# MicroControllerSTM32f103.net
KiCad netlist of a schematic drawn in Altium Designer
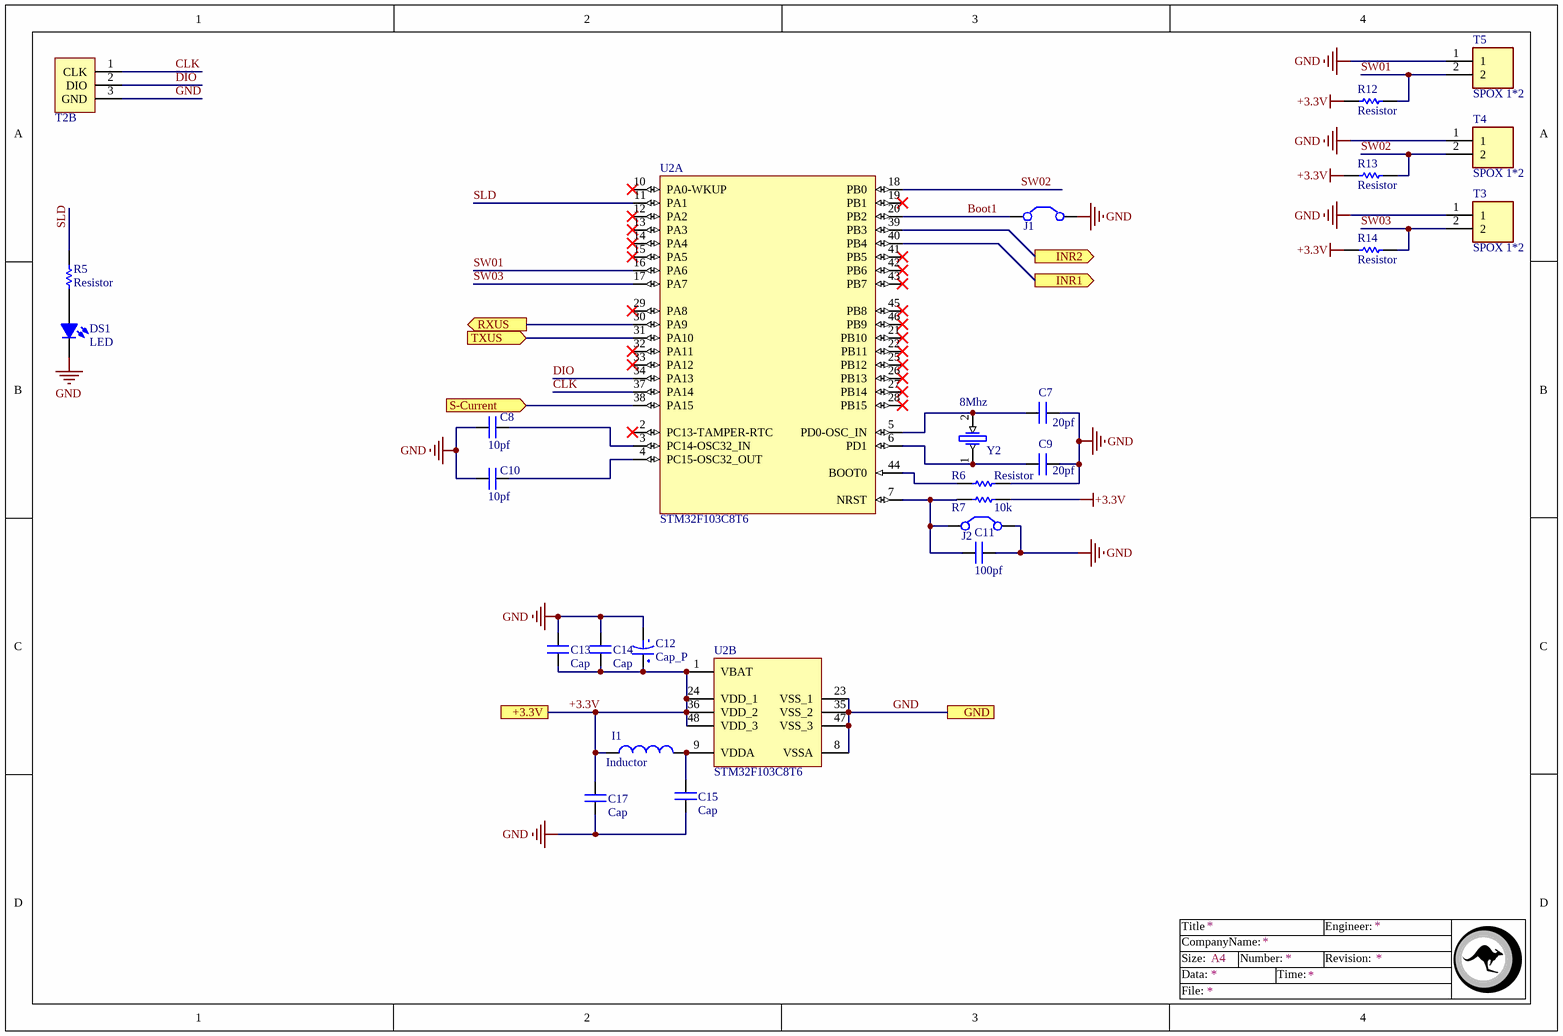
[diagram p0: MicroControllerSTM32f103.SchDoc]

(export (version "E")
  (design (tool "Eeschema 10.0.6"))
  (components
    (comp (ref "C7")
      (value "20pf")
      (footprint "Cap0805")
      (description "Surface mount Capacitor")
      (libsource (lib "PMLIB2020") (part "Cap"))
    )
    (comp (ref "C8")
      (value "10pf")
      (footprint "Cap0805")
      (description "Surface mount Capacitor")
      (libsource (lib "PMLIB2020") (part "Cap"))
    )
    (comp (ref "C9")
      (value "20pf")
      (footprint "Cap0805")
      (description "Surface mount Capacitor")
      (libsource (lib "PMLIB2020") (part "Cap"))
    )
    (comp (ref "C10")
      (value "10pf")
      (footprint "Cap0805")
      (description "Surface mount Capacitor")
      (libsource (lib "PMLIB2020") (part "Cap"))
    )
    (comp (ref "C11")
      (value "100pf")
      (footprint "Cap0805")
      (description "Surface mount Capacitor")
      (libsource (lib "PMLIB2020") (part "Cap"))
    )
    (comp (ref "C12")
      (value "Cap_P")
      (footprint "CAPMOL_C")
      (description "Polarity")
      (libsource (lib "PMLIB2020") (part "Cap_P"))
    )
    (comp (ref "C13")
      (value "Cap")
      (footprint "Cap0805")
      (description "Surface mount Capacitor")
      (libsource (lib "PMLIB2020") (part "Cap"))
    )
    (comp (ref "C14")
      (value "Cap")
      (footprint "Cap0805")
      (description "Surface mount Capacitor")
      (libsource (lib "PMLIB2020") (part "Cap"))
    )
    (comp (ref "C15")
      (value "Cap")
      (footprint "Cap0805")
      (description "Surface mount Capacitor")
      (libsource (lib "PMLIB2020") (part "Cap"))
    )
    (comp (ref "C17")
      (value "Cap")
      (footprint "Cap0805")
      (description "Surface mount Capacitor")
      (libsource (lib "PMLIB2020") (part "Cap"))
    )
    (comp (ref "DS1") (value "LED") (footprint "Led0805") (libsource (lib "PMLIB2020") (part "LED")))
    (comp (ref "I1")
      (value "Inductor")
      (footprint "1206")
      (description "Indicator")
      (libsource (lib "PMLIB2020") (part "Inductor"))
    )
    (comp (ref "J1")
      (value "Jumper")
      (footprint "Jumper SMD - Small")
      (libsource (lib "PMLIB2020") (part "Jumper"))
    )
    (comp (ref "J2")
      (value "Jumper")
      (footprint "Jumper SMD - Small")
      (libsource (lib "PMLIB2020") (part "Jumper"))
    )
    (comp (ref "R5") (value "Resistor") (footprint "R0805") (libsource (lib "PMLIB2020") (part "Resistor")))
    (comp (ref "R6") (value "Resistor") (footprint "R0805") (libsource (lib "PMLIB2020") (part "Resistor")))
    (comp (ref "R7")
      (value "10k")
      (footprint "R0805")
      (description "Resistor")
      (libsource (lib "PMLIB2020") (part "Resistor"))
    )
    (comp (ref "R12")
      (value "Resistor")
      (footprint "0603")
      (libsource (lib "PMLIB2020-V3") (part "Resistor"))
    )
    (comp (ref "R13")
      (value "Resistor")
      (footprint "0603")
      (libsource (lib "PMLIB2020-V3") (part "Resistor"))
    )
    (comp (ref "R14")
      (value "Resistor")
      (footprint "0603")
      (libsource (lib "PMLIB2020-V3") (part "Resistor"))
    )
    (comp (ref "T2")
      (value "Serial Program")
      (footprint "MHDR1X03-254P - E")
      (description "STM Serial Program pin")
      (libsource (lib "PMLIB2020") (part "Serial Program"))
    )
    (comp (ref "T3")
      (value "SPOX 1*2")
      (footprint "SPOX2")
      (libsource (lib "PMLIB2020-V3") (part "SPOX 1*2"))
    )
    (comp (ref "T4")
      (value "SPOX 1*2")
      (footprint "SPOX2")
      (libsource (lib "PMLIB2020-V3") (part "SPOX 1*2"))
    )
    (comp (ref "T5")
      (value "SPOX 1*2")
      (footprint "SPOX2")
      (libsource (lib "PMLIB2020-V3") (part "SPOX 1*2"))
    )
    (comp (ref "U2")
      (value "STM32F103C8T6")
      (footprint "LQFP48_L")
      (libsource (lib "STMicroelectronics STM32 F1") (part "STM32F103C8T6"))
    )
    (comp (ref "Y2")
      (value "8Mhz")
      (footprint "CrystallB")
      (description "Crystal")
      (libsource (lib "PMLIB2020") (part "Crystal"))
    )
  )
  (nets
    (net (code "1") (name "+3.3V") (class "Default")
      (node (ref "C12") (pin "2") (pinfunction "2_2") (pintype "passive"))
      (node (ref "C13") (pin "1") (pinfunction "1_1") (pintype "passive"))
      (node (ref "C14") (pin "1") (pinfunction "1_1") (pintype "passive"))
      (node (ref "C17") (pin "2") (pinfunction "2_2") (pintype "passive"))
      (node (ref "I1") (pin "1") (pinfunction "1_1") (pintype "passive"))
      (node (ref "R12") (pin "1") (pinfunction "1_1") (pintype "passive"))
      (node (ref "R13") (pin "1") (pinfunction "1_1") (pintype "passive"))
      (node (ref "R14") (pin "1") (pinfunction "1_1") (pintype "passive"))
      (node (ref "R7") (pin "1") (pinfunction "1_1") (pintype "passive"))
      (node (ref "U2") (pin "1") (pinfunction "VBAT_1") (pintype "power_in"))
      (node (ref "U2") (pin "24") (pinfunction "VDD_1_24") (pintype "power_in"))
      (node (ref "U2") (pin "36") (pinfunction "VDD_2_36") (pintype "power_in"))
      (node (ref "U2") (pin "48") (pinfunction "VDD_3_48") (pintype "power_in"))
    )
    (net (code "2") (name "/Boot1") (class "Default")
      (node (ref "J1") (pin "1") (pinfunction "C1_1") (pintype "passive"))
      (node (ref "U2") (pin "20") (pinfunction "PB2_20") (pintype "bidirectional"))
    )
    (net (code "3") (name "/CLK") (class "Default")
      (node (ref "T2") (pin "1") (pinfunction "CLK_1") (pintype "passive"))
      (node (ref "U2") (pin "37") (pinfunction "PA14_37") (pintype "bidirectional"))
    )
    (net (code "4") (name "/DIO") (class "Default")
      (node (ref "T2") (pin "2") (pinfunction "DIO_2") (pintype "passive"))
      (node (ref "U2") (pin "34") (pinfunction "PA13_34") (pintype "bidirectional"))
    )
    (net (code "5") (name "/INR1") (class "Default")
      (node (ref "U2") (pin "40") (pinfunction "PB4_40") (pintype "bidirectional"))
    )
    (net (code "6") (name "/INR2") (class "Default")
      (node (ref "U2") (pin "39") (pinfunction "PB3_39") (pintype "bidirectional"))
    )
    (net (code "7") (name "/RXUS") (class "Default")
      (node (ref "U2") (pin "30") (pinfunction "PA9_30") (pintype "bidirectional"))
    )
    (net (code "8") (name "/S-Current") (class "Default")
      (node (ref "U2") (pin "38") (pinfunction "PA15_38") (pintype "bidirectional"))
    )
    (net (code "9") (name "/SLD") (class "Default")
      (node (ref "R5") (pin "1") (pinfunction "1_1") (pintype "passive"))
      (node (ref "U2") (pin "11") (pinfunction "PA1_11") (pintype "bidirectional"))
    )
    (net (code "10") (name "/SW01") (class "Default")
      (node (ref "R12") (pin "2") (pinfunction "2_2") (pintype "passive"))
      (node (ref "T5") (pin "2") (pinfunction "2_2") (pintype "passive"))
      (node (ref "U2") (pin "16") (pinfunction "PA6_16") (pintype "bidirectional"))
    )
    (net (code "11") (name "/SW02") (class "Default")
      (node (ref "R13") (pin "2") (pinfunction "2_2") (pintype "passive"))
      (node (ref "T4") (pin "2") (pinfunction "2_2") (pintype "passive"))
      (node (ref "U2") (pin "18") (pinfunction "PB0_18") (pintype "bidirectional"))
    )
    (net (code "12") (name "/SW03") (class "Default")
      (node (ref "R14") (pin "2") (pinfunction "2_2") (pintype "passive"))
      (node (ref "T3") (pin "2") (pinfunction "2_2") (pintype "passive"))
      (node (ref "U2") (pin "17") (pinfunction "PA7_17") (pintype "bidirectional"))
    )
    (net (code "13") (name "/TXUS") (class "Default")
      (node (ref "U2") (pin "31") (pinfunction "PA10_31") (pintype "bidirectional"))
    )
    (net (code "14") (name "GND") (class "Default")
      (node (ref "C10") (pin "1") (pinfunction "1_1") (pintype "passive"))
      (node (ref "C11") (pin "2") (pinfunction "2_2") (pintype "passive"))
      (node (ref "C12") (pin "1") (pinfunction "1_1") (pintype "passive"))
      (node (ref "C13") (pin "2") (pinfunction "2_2") (pintype "passive"))
      (node (ref "C14") (pin "2") (pinfunction "2_2") (pintype "passive"))
      (node (ref "C15") (pin "1") (pinfunction "1_1") (pintype "passive"))
      (node (ref "C17") (pin "1") (pinfunction "1_1") (pintype "passive"))
      (node (ref "C7") (pin "1") (pinfunction "1_1") (pintype "passive"))
      (node (ref "C8") (pin "1") (pinfunction "1_1") (pintype "passive"))
      (node (ref "C9") (pin "1") (pinfunction "1_1") (pintype "passive"))
      (node (ref "DS1") (pin "K") (pinfunction "K_K") (pintype "passive"))
      (node (ref "J1") (pin "2") (pinfunction "C2_2") (pintype "passive"))
      (node (ref "J2") (pin "2") (pinfunction "C2_2") (pintype "passive"))
      (node (ref "R6") (pin "2") (pinfunction "2_2") (pintype "passive"))
      (node (ref "T2") (pin "3") (pinfunction "GND_3") (pintype "passive"))
      (node (ref "T3") (pin "1") (pinfunction "1_1") (pintype "passive"))
      (node (ref "T4") (pin "1") (pinfunction "1_1") (pintype "passive"))
      (node (ref "T5") (pin "1") (pinfunction "1_1") (pintype "passive"))
      (node (ref "U2") (pin "23") (pinfunction "VSS_1_23") (pintype "power_in"))
      (node (ref "U2") (pin "35") (pinfunction "VSS_2_35") (pintype "power_in"))
      (node (ref "U2") (pin "47") (pinfunction "VSS_3_47") (pintype "power_in"))
      (node (ref "U2") (pin "8") (pinfunction "VSSA_8") (pintype "power_in"))
    )
    (net (code "15") (name "Net-(DS1-PadA)") (class "Default")
      (node (ref "DS1") (pin "A") (pinfunction "A_A") (pintype "passive"))
      (node (ref "R5") (pin "2") (pinfunction "2_2") (pintype "passive"))
    )
    (net (code "16") (name "Net-(J2-C1)") (class "Default")
      (node (ref "C11") (pin "1") (pinfunction "1_1") (pintype "passive"))
      (node (ref "J2") (pin "1") (pinfunction "C1_1") (pintype "passive"))
      (node (ref "R7") (pin "2") (pinfunction "2_2") (pintype "passive"))
      (node (ref "U2") (pin "7") (pinfunction "NRST_7") (pintype "bidirectional"))
    )
    (net (code "17") (name "Net-(U2A-BOOT0)") (class "Default")
      (node (ref "R6") (pin "1") (pinfunction "1_1") (pintype "passive"))
      (node (ref "U2") (pin "44") (pinfunction "BOOT0_44") (pintype "input"))
    )
    (net (code "18") (name "Net-(U2A-PC14-OSC32_IN)") (class "Default")
      (node (ref "C8") (pin "2") (pinfunction "2_2") (pintype "passive"))
      (node (ref "U2") (pin "3") (pinfunction "PC14-OSC32_IN_3") (pintype "bidirectional"))
    )
    (net (code "19") (name "Net-(U2A-PC15-OSC32_OUT)") (class "Default")
      (node (ref "C10") (pin "2") (pinfunction "2_2") (pintype "passive"))
      (node (ref "U2") (pin "4") (pinfunction "PC15-OSC32_OUT_4") (pintype "bidirectional"))
    )
    (net (code "20") (name "Net-(U2A-PD0-OSC_IN)") (class "Default")
      (node (ref "C7") (pin "2") (pinfunction "2_2") (pintype "passive"))
      (node (ref "U2") (pin "5") (pinfunction "PD0-OSC_IN_5") (pintype "bidirectional"))
      (node (ref "Y2") (pin "2") (pinfunction "2_2") (pintype "input"))
    )
    (net (code "21") (name "Net-(U2A-PD1)") (class "Default")
      (node (ref "C9") (pin "2") (pinfunction "2_2") (pintype "passive"))
      (node (ref "U2") (pin "6") (pinfunction "PD1_6") (pintype "bidirectional"))
      (node (ref "Y2") (pin "1") (pinfunction "1_1") (pintype "output"))
    )
    (net (code "22") (name "Net-(U2B-VDDA)") (class "Default")
      (node (ref "C15") (pin "2") (pinfunction "2_2") (pintype "passive"))
      (node (ref "I1") (pin "2") (pinfunction "2_2") (pintype "passive"))
      (node (ref "U2") (pin "9") (pinfunction "VDDA_9") (pintype "power_in"))
    )
    (net (code "23") (name "unconnected-(U2A-PA0-WKUP-Pad10)") (class "Default")
      (node (ref "U2") (pin "10") (pinfunction "PA0-WKUP_10") (pintype "bidirectional+no_connect"))
    )
    (net (code "24") (name "unconnected-(U2A-PA2-Pad12)") (class "Default")
      (node (ref "U2") (pin "12") (pinfunction "PA2_12") (pintype "bidirectional+no_connect"))
    )
    (net (code "25") (name "unconnected-(U2A-PA3-Pad13)") (class "Default")
      (node (ref "U2") (pin "13") (pinfunction "PA3_13") (pintype "bidirectional+no_connect"))
    )
    (net (code "26") (name "unconnected-(U2A-PA4-Pad14)") (class "Default")
      (node (ref "U2") (pin "14") (pinfunction "PA4_14") (pintype "bidirectional+no_connect"))
    )
    (net (code "27") (name "unconnected-(U2A-PA5-Pad15)") (class "Default")
      (node (ref "U2") (pin "15") (pinfunction "PA5_15") (pintype "bidirectional+no_connect"))
    )
    (net (code "28") (name "unconnected-(U2A-PA8-Pad29)") (class "Default")
      (node (ref "U2") (pin "29") (pinfunction "PA8_29") (pintype "bidirectional+no_connect"))
    )
    (net (code "29") (name "unconnected-(U2A-PA11-Pad32)") (class "Default")
      (node (ref "U2") (pin "32") (pinfunction "PA11_32") (pintype "bidirectional+no_connect"))
    )
    (net (code "30") (name "unconnected-(U2A-PA12-Pad33)") (class "Default")
      (node (ref "U2") (pin "33") (pinfunction "PA12_33") (pintype "bidirectional+no_connect"))
    )
    (net (code "31") (name "unconnected-(U2A-PB1-Pad19)") (class "Default")
      (node (ref "U2") (pin "19") (pinfunction "PB1_19") (pintype "bidirectional+no_connect"))
    )
    (net (code "32") (name "unconnected-(U2A-PB5-Pad41)") (class "Default")
      (node (ref "U2") (pin "41") (pinfunction "PB5_41") (pintype "bidirectional+no_connect"))
    )
    (net (code "33") (name "unconnected-(U2A-PB6-Pad42)") (class "Default")
      (node (ref "U2") (pin "42") (pinfunction "PB6_42") (pintype "bidirectional+no_connect"))
    )
    (net (code "34") (name "unconnected-(U2A-PB7-Pad43)") (class "Default")
      (node (ref "U2") (pin "43") (pinfunction "PB7_43") (pintype "bidirectional+no_connect"))
    )
    (net (code "35") (name "unconnected-(U2A-PB8-Pad45)") (class "Default")
      (node (ref "U2") (pin "45") (pinfunction "PB8_45") (pintype "bidirectional+no_connect"))
    )
    (net (code "36") (name "unconnected-(U2A-PB9-Pad46)") (class "Default")
      (node (ref "U2") (pin "46") (pinfunction "PB9_46") (pintype "bidirectional+no_connect"))
    )
    (net (code "37") (name "unconnected-(U2A-PB10-Pad21)") (class "Default")
      (node (ref "U2") (pin "21") (pinfunction "PB10_21") (pintype "bidirectional+no_connect"))
    )
    (net (code "38") (name "unconnected-(U2A-PB11-Pad22)") (class "Default")
      (node (ref "U2") (pin "22") (pinfunction "PB11_22") (pintype "bidirectional+no_connect"))
    )
    (net (code "39") (name "unconnected-(U2A-PB12-Pad25)") (class "Default")
      (node (ref "U2") (pin "25") (pinfunction "PB12_25") (pintype "bidirectional+no_connect"))
    )
    (net (code "40") (name "unconnected-(U2A-PB13-Pad26)") (class "Default")
      (node (ref "U2") (pin "26") (pinfunction "PB13_26") (pintype "bidirectional+no_connect"))
    )
    (net (code "41") (name "unconnected-(U2A-PB14-Pad27)") (class "Default")
      (node (ref "U2") (pin "27") (pinfunction "PB14_27") (pintype "bidirectional+no_connect"))
    )
    (net (code "42") (name "unconnected-(U2A-PB15-Pad28)") (class "Default")
      (node (ref "U2") (pin "28") (pinfunction "PB15_28") (pintype "bidirectional+no_connect"))
    )
    (net (code "43") (name "unconnected-(U2A-PC13-TAMPER-RTC-Pad2)") (class "Default")
      (node (ref "U2") (pin "2") (pinfunction "PC13-TAMPER-RTC_2") (pintype "bidirectional+no_connect"))
    )
  )
)
